# PaxGeo_MoBo.net
KiCad netlist of a schematic drawn in EAGLE
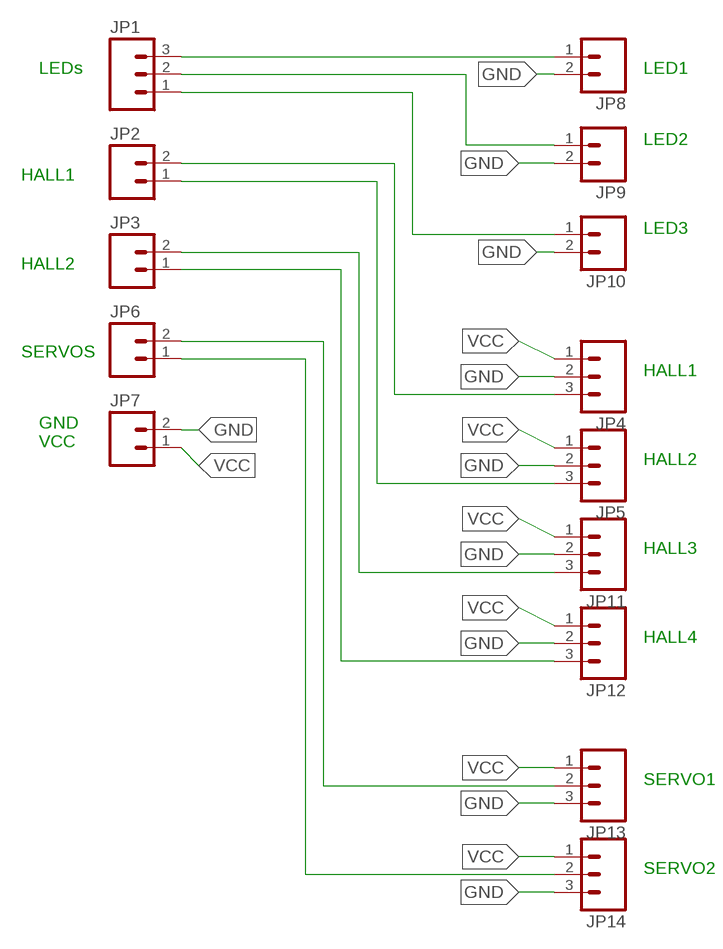
[diagram p0: schematic, sheet 1]

(export (version "E")
  (design (tool "Eeschema 10.0.6"))
  (components
    (comp (ref "JP1")
      (value "M03SCREW")
      (footprint "eagle-import:SCREWTERMINAL-3.5MM-3")
      (libsource (lib "eagle-import") (part "M03SCREW"))
    )
    (comp (ref "JP2")
      (value "M023.5MM")
      (footprint "eagle-import:SCREWTERMINAL-3.5MM-2")
      (libsource (lib "eagle-import") (part "M023.5MM"))
    )
    (comp (ref "JP3")
      (value "M023.5MM")
      (footprint "eagle-import:SCREWTERMINAL-3.5MM-2")
      (libsource (lib "eagle-import") (part "M023.5MM"))
    )
    (comp (ref "JP4")
      (value "M03SCREW")
      (footprint "eagle-import:SCREWTERMINAL-3.5MM-3")
      (libsource (lib "eagle-import") (part "M03SCREW"))
    )
    (comp (ref "JP5")
      (value "M03SCREW")
      (footprint "eagle-import:SCREWTERMINAL-3.5MM-3")
      (libsource (lib "eagle-import") (part "M03SCREW"))
    )
    (comp (ref "JP6")
      (value "M023.5MM")
      (footprint "eagle-import:SCREWTERMINAL-3.5MM-2")
      (libsource (lib "eagle-import") (part "M023.5MM"))
    )
    (comp (ref "JP7")
      (value "M023.5MM")
      (footprint "eagle-import:SCREWTERMINAL-3.5MM-2")
      (libsource (lib "eagle-import") (part "M023.5MM"))
    )
    (comp (ref "JP8")
      (value "M023.5MM")
      (footprint "eagle-import:SCREWTERMINAL-3.5MM-2")
      (libsource (lib "eagle-import") (part "M023.5MM"))
    )
    (comp (ref "JP9")
      (value "M023.5MM")
      (footprint "eagle-import:SCREWTERMINAL-3.5MM-2")
      (libsource (lib "eagle-import") (part "M023.5MM"))
    )
    (comp (ref "JP10")
      (value "M023.5MM")
      (footprint "eagle-import:SCREWTERMINAL-3.5MM-2")
      (libsource (lib "eagle-import") (part "M023.5MM"))
    )
    (comp (ref "JP11")
      (value "M03SCREW")
      (footprint "eagle-import:SCREWTERMINAL-3.5MM-3")
      (libsource (lib "eagle-import") (part "M03SCREW"))
    )
    (comp (ref "JP12")
      (value "M03SCREW")
      (footprint "eagle-import:SCREWTERMINAL-3.5MM-3")
      (libsource (lib "eagle-import") (part "M03SCREW"))
    )
    (comp (ref "JP13")
      (value "M03SCREW")
      (footprint "eagle-import:SCREWTERMINAL-3.5MM-3")
      (libsource (lib "eagle-import") (part "M03SCREW"))
    )
    (comp (ref "JP14")
      (value "M03SCREW")
      (footprint "eagle-import:SCREWTERMINAL-3.5MM-3")
      (libsource (lib "eagle-import") (part "M03SCREW"))
    )
  )
  (nets
    (net (code "1") (name "GND") (class "Default")
      (node (ref "JP10") (pin "2") (pinfunction "2_2") (pintype "passive"))
      (node (ref "JP11") (pin "2") (pinfunction "2_2") (pintype "passive"))
      (node (ref "JP12") (pin "2") (pinfunction "2_2") (pintype "passive"))
      (node (ref "JP13") (pin "3") (pinfunction "3_3") (pintype "passive"))
      (node (ref "JP14") (pin "3") (pinfunction "3_3") (pintype "passive"))
      (node (ref "JP4") (pin "2") (pinfunction "2_2") (pintype "passive"))
      (node (ref "JP5") (pin "2") (pinfunction "2_2") (pintype "passive"))
      (node (ref "JP7") (pin "2") (pinfunction "2_2") (pintype "passive"))
      (node (ref "JP8") (pin "2") (pinfunction "2_2") (pintype "passive"))
      (node (ref "JP9") (pin "2") (pinfunction "2_2") (pintype "passive"))
    )
    (net (code "2") (name "Net-(JP1-Pad1)") (class "Default")
      (node (ref "JP1") (pin "1") (pinfunction "1_1") (pintype "passive"))
      (node (ref "JP10") (pin "1") (pinfunction "1_1") (pintype "passive"))
    )
    (net (code "3") (name "Net-(JP1-Pad2)") (class "Default")
      (node (ref "JP1") (pin "2") (pinfunction "2_2") (pintype "passive"))
      (node (ref "JP9") (pin "1") (pinfunction "1_1") (pintype "passive"))
    )
    (net (code "4") (name "Net-(JP1-Pad3)") (class "Default")
      (node (ref "JP1") (pin "3") (pinfunction "3_3") (pintype "passive"))
      (node (ref "JP8") (pin "1") (pinfunction "1_1") (pintype "passive"))
    )
    (net (code "5") (name "Net-(JP2-Pad1)") (class "Default")
      (node (ref "JP2") (pin "1") (pinfunction "1_1") (pintype "passive"))
      (node (ref "JP5") (pin "3") (pinfunction "3_3") (pintype "passive"))
    )
    (net (code "6") (name "Net-(JP2-Pad2)") (class "Default")
      (node (ref "JP2") (pin "2") (pinfunction "2_2") (pintype "passive"))
      (node (ref "JP4") (pin "3") (pinfunction "3_3") (pintype "passive"))
    )
    (net (code "7") (name "Net-(JP11-Pad3)") (class "Default")
      (node (ref "JP11") (pin "3") (pinfunction "3_3") (pintype "passive"))
      (node (ref "JP3") (pin "2") (pinfunction "2_2") (pintype "passive"))
    )
    (net (code "8") (name "Net-(JP12-Pad3)") (class "Default")
      (node (ref "JP12") (pin "3") (pinfunction "3_3") (pintype "passive"))
      (node (ref "JP3") (pin "1") (pinfunction "1_1") (pintype "passive"))
    )
    (net (code "9") (name "Net-(JP13-Pad2)") (class "Default")
      (node (ref "JP13") (pin "2") (pinfunction "2_2") (pintype "passive"))
      (node (ref "JP6") (pin "2") (pinfunction "2_2") (pintype "passive"))
    )
    (net (code "10") (name "Net-(JP14-Pad2)") (class "Default")
      (node (ref "JP14") (pin "2") (pinfunction "2_2") (pintype "passive"))
      (node (ref "JP6") (pin "1") (pinfunction "1_1") (pintype "passive"))
    )
    (net (code "11") (name "VCC") (class "Default")
      (node (ref "JP11") (pin "1") (pinfunction "1_1") (pintype "passive"))
      (node (ref "JP12") (pin "1") (pinfunction "1_1") (pintype "passive"))
      (node (ref "JP13") (pin "1") (pinfunction "1_1") (pintype "passive"))
      (node (ref "JP14") (pin "1") (pinfunction "1_1") (pintype "passive"))
      (node (ref "JP4") (pin "1") (pinfunction "1_1") (pintype "passive"))
      (node (ref "JP5") (pin "1") (pinfunction "1_1") (pintype "passive"))
      (node (ref "JP7") (pin "1") (pinfunction "1_1") (pintype "passive"))
    )
  )
)
